# gps-neo-n8.net
KiCad netlist of a schematic drawn in EAGLE
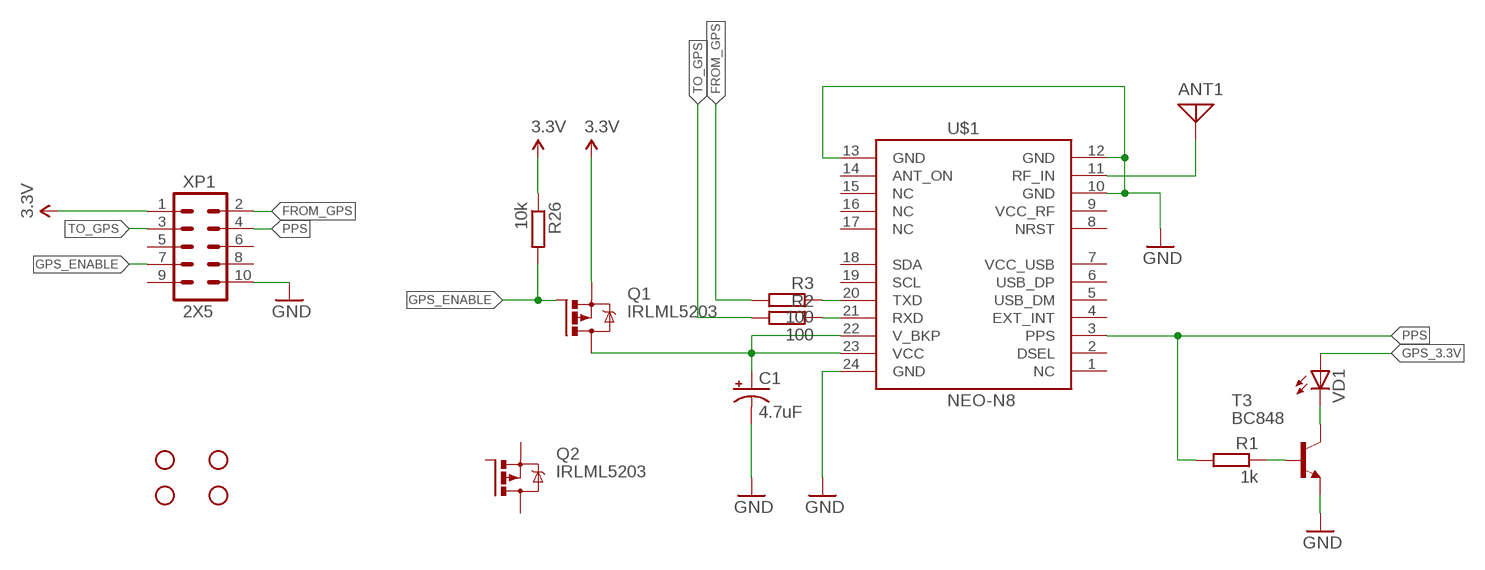
[diagram p0: schematic, sheet 1]

(export (version "E")
  (design (tool "Eeschema 10.0.6"))
  (components
    (comp (ref "ANT1")
      (value "GPS_ANTENNA'35X35'")
      (footprint "eagle-import:GPS_ANT_35X35MM")
      (libsource (lib "eagle-import") (part "GPS_ANTENNA'35X35'"))
    )
    (comp (ref "C1")
      (value "4.7uF")
      (footprint "eagle-import:EIA3216-KIT")
      (libsource (lib "eagle-import") (part "CAP_POL1206-KIT"))
    )
    (comp (ref "JP1")
      (value "STAND-OFF")
      (footprint "eagle-import:STAND-OFF")
      (libsource (lib "eagle-import") (part "STAND-OFF"))
    )
    (comp (ref "JP2")
      (value "STAND-OFF")
      (footprint "eagle-import:STAND-OFF")
      (libsource (lib "eagle-import") (part "STAND-OFF"))
    )
    (comp (ref "JP4")
      (value "STAND-OFF")
      (footprint "eagle-import:STAND-OFF")
      (libsource (lib "eagle-import") (part "STAND-OFF"))
    )
    (comp (ref "JP5")
      (value "STAND-OFF")
      (footprint "eagle-import:STAND-OFF")
      (libsource (lib "eagle-import") (part "STAND-OFF"))
    )
    (comp (ref "Q1")
      (value "IRLML5203")
      (footprint "eagle-import:MICRO3")
      (libsource (lib "eagle-import") (part "IRLML5203"))
    )
    (comp (ref "Q2")
      (value "IRLML5203")
      (footprint "eagle-import:MICRO3")
      (libsource (lib "eagle-import") (part "IRLML5203"))
    )
    (comp (ref "R1")
      (value "1k")
      (footprint "eagle-import:R0805")
      (libsource (lib "eagle-import") (part "R-EU_R0805"))
    )
    (comp (ref "R2")
      (value "100")
      (footprint "eagle-import:R0805")
      (libsource (lib "eagle-import") (part "R-EU_R0805"))
    )
    (comp (ref "R3")
      (value "100")
      (footprint "eagle-import:R0805")
      (libsource (lib "eagle-import") (part "R-EU_R0805"))
    )
    (comp (ref "R26")
      (value "10k")
      (footprint "eagle-import:R0805")
      (libsource (lib "eagle-import") (part "R-EU_R0805"))
    )
    (comp (ref "T3")
      (value "BC848")
      (footprint "eagle-import:SOT23")
      (libsource (lib "eagle-import") (part "BC848"))
    )
    (comp (ref "U$1")
      (value "NEO-N8")
      (footprint "eagle-import:NEO-M8")
      (libsource (lib "eagle-import") (part "NEO-N8"))
    )
    (comp (ref "VD1")
      (value "LED0805")
      (footprint "eagle-import:LED-0805")
      (libsource (lib "eagle-import") (part "LED0805"))
    )
    (comp (ref "XP1")
      (value "2X5")
      (footprint "eagle-import:2X5-PSEUDOSMD")
      (libsource (lib "eagle-import") (part "2X5"))
    )
  )
  (nets
    (net (code "1") (name "/VCC_RF") (class "Default")
      (node (ref "U$1") (pin "9") (pinfunction "VCC_RF_9") (pintype "power_in"))
    )
    (net (code "2") (name "3.3V") (class "Default")
      (node (ref "Q1") (pin "2") (pinfunction "S_2") (pintype "passive"))
      (node (ref "R26") (pin "1") (pinfunction "1_1") (pintype "passive"))
      (node (ref "XP1") (pin "1") (pinfunction "1_1") (pintype "passive"))
    )
    (net (code "3") (name "FROM_GPS") (class "Default")
      (node (ref "R3") (pin "2") (pinfunction "2_2") (pintype "passive"))
      (node (ref "XP1") (pin "2") (pinfunction "2_2") (pintype "passive"))
    )
    (net (code "4") (name "GND") (class "Default")
      (node (ref "C1") (pin "C") (pinfunction "-_C") (pintype "passive"))
      (node (ref "T3") (pin "2") (pinfunction "E_2") (pintype "passive"))
      (node (ref "U$1") (pin "10") (pinfunction "GND_10") (pintype "power_in"))
      (node (ref "U$1") (pin "12") (pinfunction "GND_12") (pintype "power_in"))
      (node (ref "U$1") (pin "13") (pinfunction "GND_13") (pintype "power_in"))
      (node (ref "U$1") (pin "24") (pinfunction "GND_24") (pintype "power_in"))
      (node (ref "XP1") (pin "10") (pinfunction "10_10") (pintype "passive"))
    )
    (net (code "5") (name "GPS_3.3V") (class "Default")
      (node (ref "C1") (pin "A") (pinfunction "+_A") (pintype "passive"))
      (node (ref "Q1") (pin "3") (pinfunction "D_3") (pintype "passive"))
      (node (ref "U$1") (pin "22") (pinfunction "V_BKP_22") (pintype "power_in"))
      (node (ref "U$1") (pin "23") (pinfunction "VCC_23") (pintype "power_in"))
      (node (ref "VD1") (pin "A") (pinfunction "A_A") (pintype "passive"))
    )
    (net (code "6") (name "GPS_ENABLE") (class "Default")
      (node (ref "Q1") (pin "1") (pinfunction "G_1") (pintype "passive"))
      (node (ref "R26") (pin "2") (pinfunction "2_2") (pintype "passive"))
      (node (ref "XP1") (pin "7") (pinfunction "7_7") (pintype "passive"))
    )
    (net (code "7") (name "Net-(T3-B)") (class "Default")
      (node (ref "R1") (pin "1") (pinfunction "1_1") (pintype "passive"))
      (node (ref "T3") (pin "1") (pinfunction "B_1") (pintype "passive"))
    )
    (net (code "8") (name "Net-(T3-C)") (class "Default")
      (node (ref "T3") (pin "3") (pinfunction "C_3") (pintype "passive"))
      (node (ref "VD1") (pin "C") (pinfunction "C_C") (pintype "passive"))
    )
    (net (code "9") (name "Net-(U$1-RF_IN)") (class "Default")
      (node (ref "ANT1") (pin "1") (pinfunction "1_1") (pintype "passive"))
      (node (ref "U$1") (pin "11") (pinfunction "RF_IN_11") (pintype "input"))
    )
    (net (code "10") (name "Net-(U$1-RXD)") (class "Default")
      (node (ref "R2") (pin "1") (pinfunction "1_1") (pintype "passive"))
      (node (ref "U$1") (pin "21") (pinfunction "RXD_21") (pintype "input"))
    )
    (net (code "11") (name "Net-(U$1-TXD)") (class "Default")
      (node (ref "R3") (pin "1") (pinfunction "1_1") (pintype "passive"))
      (node (ref "U$1") (pin "20") (pinfunction "TXD_20") (pintype "output"))
    )
    (net (code "12") (name "PPS") (class "Default")
      (node (ref "R1") (pin "2") (pinfunction "2_2") (pintype "passive"))
      (node (ref "U$1") (pin "3") (pinfunction "PPS_3") (pintype "output"))
      (node (ref "XP1") (pin "4") (pinfunction "4_4") (pintype "passive"))
    )
    (net (code "13") (name "TO_GPS") (class "Default")
      (node (ref "R2") (pin "2") (pinfunction "2_2") (pintype "passive"))
      (node (ref "XP1") (pin "3") (pinfunction "3_3") (pintype "passive"))
    )
    (net (code "14") (name "unconnected-(Q2-D-Pad3)") (class "Default")
      (node (ref "Q2") (pin "3") (pinfunction "D_3") (pintype "passive"))
    )
    (net (code "15") (name "unconnected-(Q2-G-Pad1)") (class "Default")
      (node (ref "Q2") (pin "1") (pinfunction "G_1") (pintype "passive"))
    )
    (net (code "16") (name "unconnected-(Q2-S-Pad2)") (class "Default")
      (node (ref "Q2") (pin "2") (pinfunction "S_2") (pintype "passive"))
    )
    (net (code "17") (name "unconnected-(U$1-ANT_ON-Pad14)") (class "Default")
      (node (ref "U$1") (pin "14") (pinfunction "ANT_ON_14") (pintype "no_connect"))
    )
    (net (code "18") (name "unconnected-(U$1-DSEL-Pad2)") (class "Default")
      (node (ref "U$1") (pin "2") (pinfunction "DSEL_2") (pintype "input"))
    )
    (net (code "19") (name "unconnected-(U$1-EXT_INT-Pad4)") (class "Default")
      (node (ref "U$1") (pin "4") (pinfunction "EXT_INT_4") (pintype "bidirectional"))
    )
    (net (code "20") (name "unconnected-(U$1-NC-Pad1)") (class "Default")
      (node (ref "U$1") (pin "1") (pinfunction "NC_1") (pintype "no_connect"))
    )
    (net (code "21") (name "unconnected-(U$1-NC-Pad15)") (class "Default")
      (node (ref "U$1") (pin "15") (pinfunction "NC_15") (pintype "no_connect"))
    )
    (net (code "22") (name "unconnected-(U$1-NC-Pad16)") (class "Default")
      (node (ref "U$1") (pin "16") (pinfunction "NC_16") (pintype "no_connect"))
    )
    (net (code "23") (name "unconnected-(U$1-NC-Pad17)") (class "Default")
      (node (ref "U$1") (pin "17") (pinfunction "NC_17") (pintype "no_connect"))
    )
    (net (code "24") (name "unconnected-(U$1-NRST-Pad8)") (class "Default")
      (node (ref "U$1") (pin "8") (pinfunction "NRST_8") (pintype "input"))
    )
    (net (code "25") (name "unconnected-(U$1-SCL-Pad19)") (class "Default")
      (node (ref "U$1") (pin "19") (pinfunction "SCL_19") (pintype "bidirectional"))
    )
    (net (code "26") (name "unconnected-(U$1-SDA-Pad18)") (class "Default")
      (node (ref "U$1") (pin "18") (pinfunction "SDA_18") (pintype "bidirectional"))
    )
    (net (code "27") (name "unconnected-(U$1-USB_DM-Pad5)") (class "Default")
      (node (ref "U$1") (pin "5") (pinfunction "USB_DM_5") (pintype "bidirectional"))
    )
    (net (code "28") (name "unconnected-(U$1-USB_DP-Pad6)") (class "Default")
      (node (ref "U$1") (pin "6") (pinfunction "USB_DP_6") (pintype "bidirectional"))
    )
    (net (code "29") (name "unconnected-(U$1-VCC_USB-Pad7)") (class "Default")
      (node (ref "U$1") (pin "7") (pinfunction "VCC_USB_7") (pintype "input"))
    )
    (net (code "30") (name "unconnected-(XP1-Pad5)") (class "Default")
      (node (ref "XP1") (pin "5") (pinfunction "5_5") (pintype "passive"))
    )
    (net (code "31") (name "unconnected-(XP1-Pad6)") (class "Default")
      (node (ref "XP1") (pin "6") (pinfunction "6_6") (pintype "passive"))
    )
    (net (code "32") (name "unconnected-(XP1-Pad8)") (class "Default")
      (node (ref "XP1") (pin "8") (pinfunction "8_8") (pintype "passive"))
    )
    (net (code "33") (name "unconnected-(XP1-Pad9)") (class "Default")
      (node (ref "XP1") (pin "9") (pinfunction "9_9") (pintype "passive"))
    )
  )
)
